# 2030_Switches.net
KiCad netlist of a schematic drawn in EAGLE
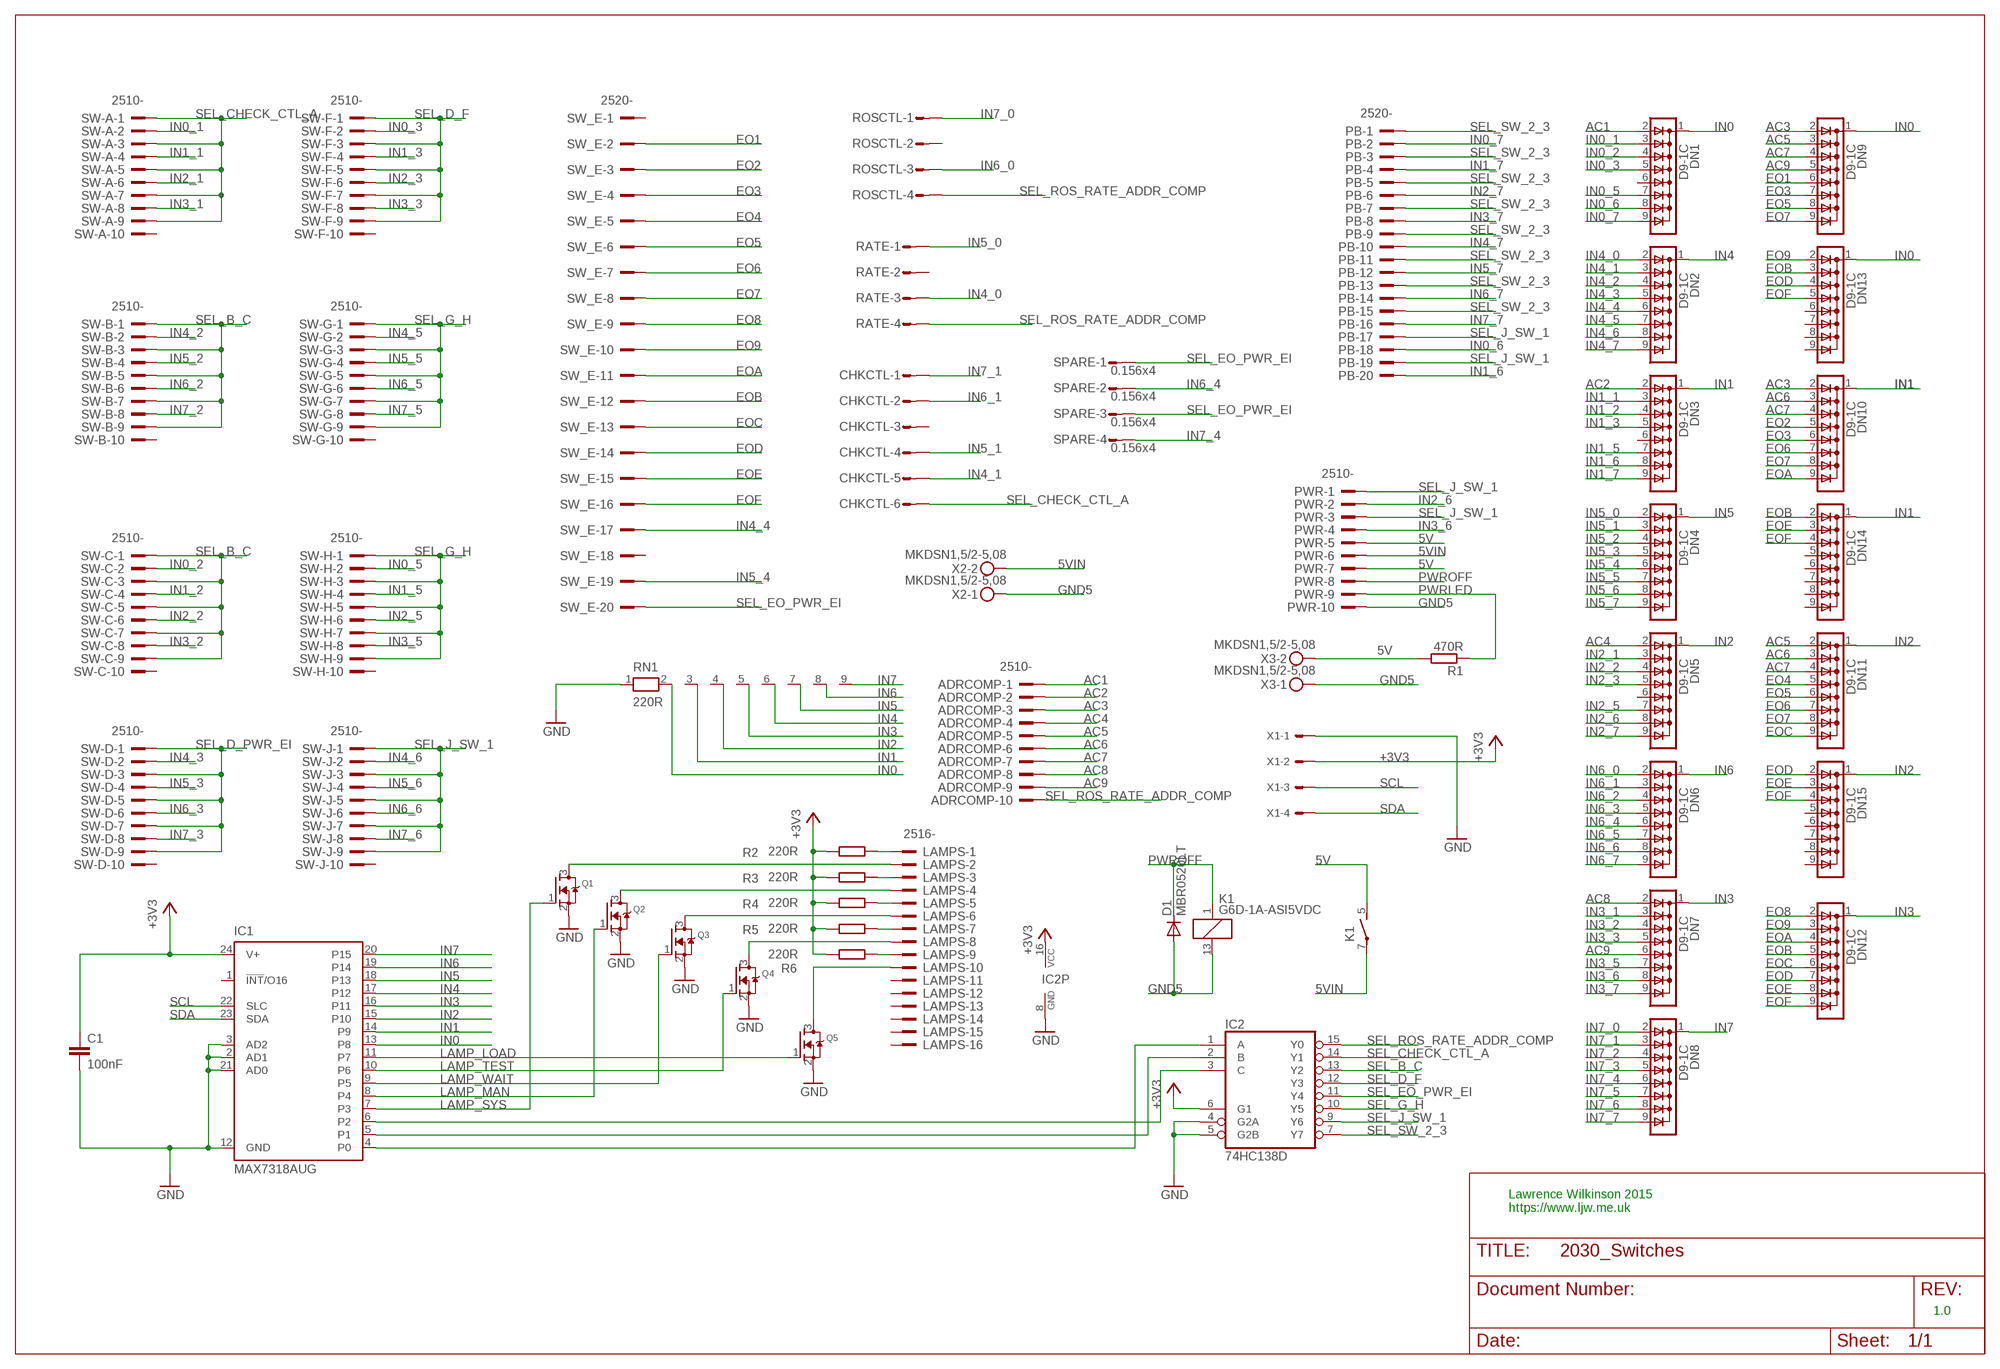
[diagram p0: schematic, sheet 1]

(export (version "E")
  (design (tool "Eeschema 10.0.6"))
  (components
    (comp (ref "ADRCOMP")
      (value "2510-")
      (footprint "eagle-import:PAK100_2500-10")
      (fields (field (name "MF") "3M") (field (name "MPN") "2510-6002UB"))
      (libsource (lib "eagle-import") (part "2510-"))
    )
    (comp (ref "C1")
      (value "100nF")
      (footprint "eagle-import:C1206")
      (libsource (lib "eagle-import") (part "C-EUC1206"))
    )
    (comp (ref "CHKCTL")
      (value "S06P")
      (footprint "eagle-import:S06P")
      (libsource (lib "eagle-import") (part "S06P"))
    )
    (comp (ref "D1")
      (value "MBR0520LT")
      (footprint "eagle-import:SOD123")
      (libsource (lib "eagle-import") (part "MBR0520LT"))
    )
    (comp (ref "DN1")
      (value "D9-1C")
      (footprint "eagle-import:SIL09C")
      (libsource (lib "eagle-import") (part "D9-1C"))
    )
    (comp (ref "DN2")
      (value "D9-1C")
      (footprint "eagle-import:SIL09C")
      (libsource (lib "eagle-import") (part "D9-1C"))
    )
    (comp (ref "DN3")
      (value "D9-1C")
      (footprint "eagle-import:SIL09C")
      (libsource (lib "eagle-import") (part "D9-1C"))
    )
    (comp (ref "DN4")
      (value "D9-1C")
      (footprint "eagle-import:SIL09C")
      (libsource (lib "eagle-import") (part "D9-1C"))
    )
    (comp (ref "DN5")
      (value "D9-1C")
      (footprint "eagle-import:SIL09C")
      (libsource (lib "eagle-import") (part "D9-1C"))
    )
    (comp (ref "DN6")
      (value "D9-1C")
      (footprint "eagle-import:SIL09C")
      (libsource (lib "eagle-import") (part "D9-1C"))
    )
    (comp (ref "DN7")
      (value "D9-1C")
      (footprint "eagle-import:SIL09C")
      (libsource (lib "eagle-import") (part "D9-1C"))
    )
    (comp (ref "DN8")
      (value "D9-1C")
      (footprint "eagle-import:SIL09C")
      (libsource (lib "eagle-import") (part "D9-1C"))
    )
    (comp (ref "DN9")
      (value "D9-1C")
      (footprint "eagle-import:SIL09C")
      (libsource (lib "eagle-import") (part "D9-1C"))
    )
    (comp (ref "DN10")
      (value "D9-1C")
      (footprint "eagle-import:SIL09C")
      (libsource (lib "eagle-import") (part "D9-1C"))
    )
    (comp (ref "DN11")
      (value "D9-1C")
      (footprint "eagle-import:SIL09C")
      (libsource (lib "eagle-import") (part "D9-1C"))
    )
    (comp (ref "DN12")
      (value "D9-1C")
      (footprint "eagle-import:SIL09C")
      (libsource (lib "eagle-import") (part "D9-1C"))
    )
    (comp (ref "DN13")
      (value "D9-1C")
      (footprint "eagle-import:SIL09C")
      (libsource (lib "eagle-import") (part "D9-1C"))
    )
    (comp (ref "DN14")
      (value "D9-1C")
      (footprint "eagle-import:SIL09C")
      (libsource (lib "eagle-import") (part "D9-1C"))
    )
    (comp (ref "DN15")
      (value "D9-1C")
      (footprint "eagle-import:SIL09C")
      (libsource (lib "eagle-import") (part "D9-1C"))
    )
    (comp (ref "IC1")
      (value "MAX7318AUG")
      (footprint "eagle-import:SO24L")
      (libsource (lib "eagle-import") (part "MAX7313AEGSOIC"))
    )
    (comp (ref "IC2")
      (value "74HC138D")
      (footprint "eagle-import:SO16")
      (libsource (lib "eagle-import") (part "74138DHC"))
    )
    (comp (ref "K1")
      (value "G6D-1A-ASI5VDC")
      (footprint "eagle-import:G6D")
      (libsource (lib "eagle-import") (part "G6D?-1A-ASI5VDC"))
    )
    (comp (ref "LAMPS")
      (value "2516-")
      (footprint "eagle-import:PAK100_2500-16")
      (libsource (lib "eagle-import") (part "2516-"))
    )
    (comp (ref "PB")
      (value "2520-")
      (footprint "eagle-import:PAK100_2500-20")
      (libsource (lib "eagle-import") (part "2520-"))
    )
    (comp (ref "PWR")
      (value "2510-")
      (footprint "eagle-import:PAK100_2500-10")
      (fields (field (name "MF") "3M") (field (name "MPN") "2510-6002UB"))
      (libsource (lib "eagle-import") (part "2510-"))
    )
    (comp (ref "Q1")
      (value "MOSFET-NREFLOW")
      (footprint "eagle-import:SOT23")
      (libsource (lib "eagle-import") (part "MOSFET-NREFLOW"))
    )
    (comp (ref "Q2")
      (value "MOSFET-NREFLOW")
      (footprint "eagle-import:SOT23")
      (libsource (lib "eagle-import") (part "MOSFET-NREFLOW"))
    )
    (comp (ref "Q3")
      (value "MOSFET-NREFLOW")
      (footprint "eagle-import:SOT23")
      (libsource (lib "eagle-import") (part "MOSFET-NREFLOW"))
    )
    (comp (ref "Q4")
      (value "MOSFET-NREFLOW")
      (footprint "eagle-import:SOT23")
      (libsource (lib "eagle-import") (part "MOSFET-NREFLOW"))
    )
    (comp (ref "Q5")
      (value "MOSFET-NREFLOW")
      (footprint "eagle-import:SOT23")
      (libsource (lib "eagle-import") (part "MOSFET-NREFLOW"))
    )
    (comp (ref "R1")
      (value "470R")
      (footprint "eagle-import:M1206")
      (libsource (lib "eagle-import") (part "R-EU_M1206"))
    )
    (comp (ref "R2")
      (value "220R")
      (footprint "eagle-import:R0805")
      (libsource (lib "eagle-import") (part "R-EU_R0805"))
    )
    (comp (ref "R3")
      (value "220R")
      (footprint "eagle-import:R0805")
      (libsource (lib "eagle-import") (part "R-EU_R0805"))
    )
    (comp (ref "R4")
      (value "220R")
      (footprint "eagle-import:R0805")
      (libsource (lib "eagle-import") (part "R-EU_R0805"))
    )
    (comp (ref "R5")
      (value "220R")
      (footprint "eagle-import:R0805")
      (libsource (lib "eagle-import") (part "R-EU_R0805"))
    )
    (comp (ref "R6")
      (value "220R")
      (footprint "eagle-import:R0805")
      (libsource (lib "eagle-import") (part "R-EU_R0805"))
    )
    (comp (ref "RATE")
      (value "S04P")
      (footprint "eagle-import:S04P")
      (libsource (lib "eagle-import") (part "S04P"))
    )
    (comp (ref "RN1")
      (value "220R")
      (footprint "eagle-import:RN-9")
      (libsource (lib "eagle-import") (part "RN08"))
    )
    (comp (ref "ROSCTL")
      (value "S04P")
      (footprint "eagle-import:S04P")
      (libsource (lib "eagle-import") (part "S04P"))
    )
    (comp (ref "SPARE")
      (value "0.156x4")
      (footprint "eagle-import:S04P")
      (libsource (lib "eagle-import") (part "S04P"))
    )
    (comp (ref "SW-A")
      (value "2510-")
      (footprint "eagle-import:PAK100_2500-10")
      (fields (field (name "MF") "3M") (field (name "MPN") "2510-6002UB"))
      (libsource (lib "eagle-import") (part "2510-"))
    )
    (comp (ref "SW-B")
      (value "2510-")
      (footprint "eagle-import:PAK100_2500-10")
      (fields (field (name "MF") "3M") (field (name "MPN") "2510-6002UB"))
      (libsource (lib "eagle-import") (part "2510-"))
    )
    (comp (ref "SW-C")
      (value "2510-")
      (footprint "eagle-import:PAK100_2500-10")
      (fields (field (name "MF") "3M") (field (name "MPN") "2510-6002UB"))
      (libsource (lib "eagle-import") (part "2510-"))
    )
    (comp (ref "SW-D")
      (value "2510-")
      (footprint "eagle-import:PAK100_2500-10")
      (fields (field (name "MF") "3M") (field (name "MPN") "2510-6002UB"))
      (libsource (lib "eagle-import") (part "2510-"))
    )
    (comp (ref "SW-F")
      (value "2510-")
      (footprint "eagle-import:PAK100_2500-10")
      (fields (field (name "MF") "3M") (field (name "MPN") "2510-6002UB"))
      (libsource (lib "eagle-import") (part "2510-"))
    )
    (comp (ref "SW-G")
      (value "2510-")
      (footprint "eagle-import:PAK100_2500-10")
      (fields (field (name "MF") "3M") (field (name "MPN") "2510-6002UB"))
      (libsource (lib "eagle-import") (part "2510-"))
    )
    (comp (ref "SW-H")
      (value "2510-")
      (footprint "eagle-import:PAK100_2500-10")
      (fields (field (name "MF") "3M") (field (name "MPN") "2510-6002UB"))
      (libsource (lib "eagle-import") (part "2510-"))
    )
    (comp (ref "SW-J")
      (value "2510-")
      (footprint "eagle-import:PAK100_2500-10")
      (fields (field (name "MF") "3M") (field (name "MPN") "2510-6002UB"))
      (libsource (lib "eagle-import") (part "2510-"))
    )
    (comp (ref "SW_E")
      (value "2520-")
      (footprint "eagle-import:PAK100_2500-20")
      (libsource (lib "eagle-import") (part "2520-"))
    )
    (comp (ref "X1")
      (value "KK-156-4")
      (footprint "eagle-import:KK-156-4")
      (libsource (lib "eagle-import") (part "KK-156-4"))
    )
    (comp (ref "X2")
      (value "MKDSN1,5/2-5,08")
      (footprint "eagle-import:MKDSN1,5_2-5,08")
      (libsource (lib "eagle-import") (part "MKDSN1,5/2-5,08"))
    )
    (comp (ref "X3")
      (value "MKDSN1,5/2-5,08")
      (footprint "eagle-import:MKDSN1,5_2-5,08")
      (libsource (lib "eagle-import") (part "MKDSN1,5/2-5,08"))
    )
  )
  (nets
    (net (code "1") (name "+3V3") (class "Default")
      (node (ref "C1") (pin "1") (pinfunction "1_1") (pintype "passive"))
      (node (ref "IC1") (pin "24") (pinfunction "V+_24") (pintype "power_in"))
      (node (ref "IC2") (pin "16") (pinfunction "VCC_16") (pintype "power_in"))
      (node (ref "IC2") (pin "6") (pinfunction "G1_6") (pintype "input"))
      (node (ref "R2") (pin "1") (pinfunction "1_1") (pintype "passive"))
      (node (ref "R3") (pin "1") (pinfunction "1_1") (pintype "passive"))
      (node (ref "R4") (pin "1") (pinfunction "1_1") (pintype "passive"))
      (node (ref "R5") (pin "1") (pinfunction "1_1") (pintype "passive"))
      (node (ref "R6") (pin "1") (pinfunction "1_1") (pintype "passive"))
      (node (ref "X1") (pin "2") (pinfunction "S_2") (pintype "passive"))
    )
    (net (code "2") (name "/5V") (class "Default")
      (node (ref "K1") (pin "5") (pinfunction "S_5") (pintype "passive"))
      (node (ref "PWR") (pin "5") (pinfunction "KL_5") (pintype "passive"))
      (node (ref "PWR") (pin "7") (pinfunction "KL_7") (pintype "passive"))
      (node (ref "R1") (pin "2") (pinfunction "2_2") (pintype "passive"))
      (node (ref "X3") (pin "2") (pinfunction "KL_2") (pintype "passive"))
    )
    (net (code "3") (name "/5VIN") (class "Default")
      (node (ref "K1") (pin "7") (pinfunction "P_7") (pintype "passive"))
      (node (ref "PWR") (pin "6") (pinfunction "KL_6") (pintype "passive"))
      (node (ref "X2") (pin "2") (pinfunction "KL_2") (pintype "passive"))
    )
    (net (code "4") (name "/AC1") (class "Default")
      (node (ref "ADRCOMP") (pin "1") (pinfunction "KL_1") (pintype "passive"))
      (node (ref "DN1") (pin "2") (pinfunction "2_2") (pintype "passive"))
    )
    (net (code "5") (name "/AC2") (class "Default")
      (node (ref "ADRCOMP") (pin "2") (pinfunction "KL_2") (pintype "passive"))
      (node (ref "DN3") (pin "2") (pinfunction "2_2") (pintype "passive"))
    )
    (net (code "6") (name "/AC3") (class "Default")
      (node (ref "ADRCOMP") (pin "3") (pinfunction "KL_3") (pintype "passive"))
      (node (ref "DN10") (pin "2") (pinfunction "2_2") (pintype "passive"))
      (node (ref "DN9") (pin "2") (pinfunction "2_2") (pintype "passive"))
    )
    (net (code "7") (name "/AC4") (class "Default")
      (node (ref "ADRCOMP") (pin "4") (pinfunction "KL_4") (pintype "passive"))
      (node (ref "DN5") (pin "2") (pinfunction "2_2") (pintype "passive"))
    )
    (net (code "8") (name "/AC5") (class "Default")
      (node (ref "ADRCOMP") (pin "5") (pinfunction "KL_5") (pintype "passive"))
      (node (ref "DN11") (pin "2") (pinfunction "2_2") (pintype "passive"))
      (node (ref "DN9") (pin "3") (pinfunction "3_3") (pintype "passive"))
    )
    (net (code "9") (name "/AC6") (class "Default")
      (node (ref "ADRCOMP") (pin "6") (pinfunction "KL_6") (pintype "passive"))
      (node (ref "DN10") (pin "3") (pinfunction "3_3") (pintype "passive"))
      (node (ref "DN11") (pin "3") (pinfunction "3_3") (pintype "passive"))
    )
    (net (code "10") (name "/AC7") (class "Default")
      (node (ref "ADRCOMP") (pin "7") (pinfunction "KL_7") (pintype "passive"))
      (node (ref "DN10") (pin "4") (pinfunction "4_4") (pintype "passive"))
      (node (ref "DN11") (pin "4") (pinfunction "4_4") (pintype "passive"))
      (node (ref "DN9") (pin "4") (pinfunction "4_4") (pintype "passive"))
    )
    (net (code "11") (name "/AC8") (class "Default")
      (node (ref "ADRCOMP") (pin "8") (pinfunction "KL_8") (pintype "passive"))
      (node (ref "DN7") (pin "2") (pinfunction "2_2") (pintype "passive"))
    )
    (net (code "12") (name "/AC9") (class "Default")
      (node (ref "ADRCOMP") (pin "9") (pinfunction "KL_9") (pintype "passive"))
      (node (ref "DN7") (pin "6") (pinfunction "6_6") (pintype "passive"))
      (node (ref "DN9") (pin "5") (pinfunction "5_5") (pintype "passive"))
    )
    (net (code "13") (name "/EO1") (class "Default")
      (node (ref "DN9") (pin "6") (pinfunction "6_6") (pintype "passive"))
      (node (ref "SW_E") (pin "2") (pinfunction "KL_2") (pintype "passive"))
    )
    (net (code "14") (name "/EO2") (class "Default")
      (node (ref "DN10") (pin "5") (pinfunction "5_5") (pintype "passive"))
      (node (ref "SW_E") (pin "3") (pinfunction "KL_3") (pintype "passive"))
    )
    (net (code "15") (name "/EO3") (class "Default")
      (node (ref "DN10") (pin "6") (pinfunction "6_6") (pintype "passive"))
      (node (ref "DN9") (pin "7") (pinfunction "7_7") (pintype "passive"))
      (node (ref "SW_E") (pin "4") (pinfunction "KL_4") (pintype "passive"))
    )
    (net (code "16") (name "/EO4") (class "Default")
      (node (ref "DN11") (pin "5") (pinfunction "5_5") (pintype "passive"))
      (node (ref "SW_E") (pin "5") (pinfunction "KL_5") (pintype "passive"))
    )
    (net (code "17") (name "/EO5") (class "Default")
      (node (ref "DN11") (pin "6") (pinfunction "6_6") (pintype "passive"))
      (node (ref "DN9") (pin "8") (pinfunction "8_8") (pintype "passive"))
      (node (ref "SW_E") (pin "6") (pinfunction "KL_6") (pintype "passive"))
    )
    (net (code "18") (name "/EO6") (class "Default")
      (node (ref "DN10") (pin "7") (pinfunction "7_7") (pintype "passive"))
      (node (ref "DN11") (pin "7") (pinfunction "7_7") (pintype "passive"))
      (node (ref "SW_E") (pin "7") (pinfunction "KL_7") (pintype "passive"))
    )
    (net (code "19") (name "/EO7") (class "Default")
      (node (ref "DN10") (pin "8") (pinfunction "8_8") (pintype "passive"))
      (node (ref "DN11") (pin "8") (pinfunction "8_8") (pintype "passive"))
      (node (ref "DN9") (pin "9") (pinfunction "9_9") (pintype "passive"))
      (node (ref "SW_E") (pin "8") (pinfunction "KL_8") (pintype "passive"))
    )
    (net (code "20") (name "/EO8") (class "Default")
      (node (ref "DN12") (pin "2") (pinfunction "2_2") (pintype "passive"))
      (node (ref "SW_E") (pin "9") (pinfunction "KL_9") (pintype "passive"))
    )
    (net (code "21") (name "/EO9") (class "Default")
      (node (ref "DN12") (pin "3") (pinfunction "3_3") (pintype "passive"))
      (node (ref "DN13") (pin "2") (pinfunction "2_2") (pintype "passive"))
      (node (ref "SW_E") (pin "10") (pinfunction "KL_10") (pintype "passive"))
    )
    (net (code "22") (name "/EOA") (class "Default")
      (node (ref "DN10") (pin "9") (pinfunction "9_9") (pintype "passive"))
      (node (ref "DN12") (pin "4") (pinfunction "4_4") (pintype "passive"))
      (node (ref "SW_E") (pin "11") (pinfunction "KL_11") (pintype "passive"))
    )
    (net (code "23") (name "/EOB") (class "Default")
      (node (ref "DN12") (pin "5") (pinfunction "5_5") (pintype "passive"))
      (node (ref "DN13") (pin "3") (pinfunction "3_3") (pintype "passive"))
      (node (ref "DN14") (pin "2") (pinfunction "2_2") (pintype "passive"))
      (node (ref "SW_E") (pin "12") (pinfunction "KL_12") (pintype "passive"))
    )
    (net (code "24") (name "/EOC") (class "Default")
      (node (ref "DN11") (pin "9") (pinfunction "9_9") (pintype "passive"))
      (node (ref "DN12") (pin "6") (pinfunction "6_6") (pintype "passive"))
      (node (ref "SW_E") (pin "13") (pinfunction "KL_13") (pintype "passive"))
    )
    (net (code "25") (name "/EOD") (class "Default")
      (node (ref "DN12") (pin "7") (pinfunction "7_7") (pintype "passive"))
      (node (ref "DN13") (pin "4") (pinfunction "4_4") (pintype "passive"))
      (node (ref "DN15") (pin "2") (pinfunction "2_2") (pintype "passive"))
      (node (ref "SW_E") (pin "14") (pinfunction "KL_14") (pintype "passive"))
    )
    (net (code "26") (name "/EOE") (class "Default")
      (node (ref "DN12") (pin "8") (pinfunction "8_8") (pintype "passive"))
      (node (ref "DN14") (pin "3") (pinfunction "3_3") (pintype "passive"))
      (node (ref "DN15") (pin "3") (pinfunction "3_3") (pintype "passive"))
      (node (ref "SW_E") (pin "15") (pinfunction "KL_15") (pintype "passive"))
    )
    (net (code "27") (name "/EOF") (class "Default")
      (node (ref "DN12") (pin "9") (pinfunction "9_9") (pintype "passive"))
      (node (ref "DN13") (pin "5") (pinfunction "5_5") (pintype "passive"))
      (node (ref "DN14") (pin "4") (pinfunction "4_4") (pintype "passive"))
      (node (ref "DN15") (pin "4") (pinfunction "4_4") (pintype "passive"))
      (node (ref "SW_E") (pin "16") (pinfunction "KL_16") (pintype "passive"))
    )
    (net (code "28") (name "/GND5") (class "Default")
      (node (ref "D1") (pin "A") (pinfunction "A_A") (pintype "passive"))
      (node (ref "K1") (pin "13") (pinfunction "2_13") (pintype "passive"))
      (node (ref "PWR") (pin "10") (pinfunction "KL_10") (pintype "passive"))
      (node (ref "X2") (pin "1") (pinfunction "KL_1") (pintype "passive"))
      (node (ref "X3") (pin "1") (pinfunction "KL_1") (pintype "passive"))
    )
    (net (code "29") (name "/IN0") (class "Default")
      (node (ref "DN1") (pin "1") (pinfunction "C_1") (pintype "passive"))
      (node (ref "DN13") (pin "1") (pinfunction "C_1") (pintype "passive"))
      (node (ref "DN9") (pin "1") (pinfunction "C_1") (pintype "passive"))
      (node (ref "IC1") (pin "13") (pinfunction "P8_13") (pintype "bidirectional"))
      (node (ref "RN1") (pin "2") (pinfunction "2_2") (pintype "passive"))
    )
    (net (code "30") (name "/IN0_1") (class "Default")
      (node (ref "DN1") (pin "3") (pinfunction "3_3") (pintype "passive"))
      (node (ref "SW-A") (pin "2") (pinfunction "KL_2") (pintype "passive"))
    )
    (net (code "31") (name "/IN0_2") (class "Default")
      (node (ref "DN1") (pin "4") (pinfunction "4_4") (pintype "passive"))
      (node (ref "SW-C") (pin "2") (pinfunction "KL_2") (pintype "passive"))
    )
    (net (code "32") (name "/IN0_3") (class "Default")
      (node (ref "DN1") (pin "5") (pinfunction "5_5") (pintype "passive"))
      (node (ref "SW-F") (pin "2") (pinfunction "KL_2") (pintype "passive"))
    )
    (net (code "33") (name "/IN0_5") (class "Default")
      (node (ref "DN1") (pin "7") (pinfunction "7_7") (pintype "passive"))
      (node (ref "SW-H") (pin "2") (pinfunction "KL_2") (pintype "passive"))
    )
    (net (code "34") (name "/IN0_6") (class "Default")
      (node (ref "DN1") (pin "8") (pinfunction "8_8") (pintype "passive"))
      (node (ref "PB") (pin "18") (pinfunction "KL_18") (pintype "passive"))
    )
    (net (code "35") (name "/IN0_7") (class "Default")
      (node (ref "DN1") (pin "9") (pinfunction "9_9") (pintype "passive"))
      (node (ref "PB") (pin "2") (pinfunction "KL_2") (pintype "passive"))
    )
    (net (code "36") (name "/IN1") (class "Default")
      (node (ref "DN10") (pin "1") (pinfunction "C_1") (pintype "passive"))
      (node (ref "DN14") (pin "1") (pinfunction "C_1") (pintype "passive"))
      (node (ref "DN3") (pin "1") (pinfunction "C_1") (pintype "passive"))
      (node (ref "IC1") (pin "14") (pinfunction "P9_14") (pintype "bidirectional"))
      (node (ref "RN1") (pin "3") (pinfunction "3_3") (pintype "passive"))
    )
    (net (code "37") (name "/IN1_1") (class "Default")
      (node (ref "DN3") (pin "3") (pinfunction "3_3") (pintype "passive"))
      (node (ref "SW-A") (pin "4") (pinfunction "KL_4") (pintype "passive"))
    )
    (net (code "38") (name "/IN1_2") (class "Default")
      (node (ref "DN3") (pin "4") (pinfunction "4_4") (pintype "passive"))
      (node (ref "SW-C") (pin "4") (pinfunction "KL_4") (pintype "passive"))
    )
    (net (code "39") (name "/IN1_3") (class "Default")
      (node (ref "DN3") (pin "5") (pinfunction "5_5") (pintype "passive"))
      (node (ref "SW-F") (pin "4") (pinfunction "KL_4") (pintype "passive"))
    )
    (net (code "40") (name "/IN1_5") (class "Default")
      (node (ref "DN3") (pin "7") (pinfunction "7_7") (pintype "passive"))
      (node (ref "SW-H") (pin "4") (pinfunction "KL_4") (pintype "passive"))
    )
    (net (code "41") (name "/IN1_6") (class "Default")
      (node (ref "DN3") (pin "8") (pinfunction "8_8") (pintype "passive"))
      (node (ref "PB") (pin "20") (pinfunction "KL_20") (pintype "passive"))
    )
    (net (code "42") (name "/IN1_7") (class "Default")
      (node (ref "DN3") (pin "9") (pinfunction "9_9") (pintype "passive"))
      (node (ref "PB") (pin "4") (pinfunction "KL_4") (pintype "passive"))
    )
    (net (code "43") (name "/IN2") (class "Default")
      (node (ref "DN11") (pin "1") (pinfunction "C_1") (pintype "passive"))
      (node (ref "DN15") (pin "1") (pinfunction "C_1") (pintype "passive"))
      (node (ref "DN5") (pin "1") (pinfunction "C_1") (pintype "passive"))
      (node (ref "IC1") (pin "15") (pinfunction "P10_15") (pintype "bidirectional"))
      (node (ref "RN1") (pin "4") (pinfunction "4_4") (pintype "passive"))
    )
    (net (code "44") (name "/IN2_1") (class "Default")
      (node (ref "DN5") (pin "3") (pinfunction "3_3") (pintype "passive"))
      (node (ref "SW-A") (pin "6") (pinfunction "KL_6") (pintype "passive"))
    )
    (net (code "45") (name "/IN2_2") (class "Default")
      (node (ref "DN5") (pin "4") (pinfunction "4_4") (pintype "passive"))
      (node (ref "SW-C") (pin "6") (pinfunction "KL_6") (pintype "passive"))
    )
    (net (code "46") (name "/IN2_3") (class "Default")
      (node (ref "DN5") (pin "5") (pinfunction "5_5") (pintype "passive"))
      (node (ref "SW-F") (pin "6") (pinfunction "KL_6") (pintype "passive"))
    )
    (net (code "47") (name "/IN2_5") (class "Default")
      (node (ref "DN5") (pin "7") (pinfunction "7_7") (pintype "passive"))
      (node (ref "SW-H") (pin "6") (pinfunction "KL_6") (pintype "passive"))
    )
    (net (code "48") (name "/IN2_6") (class "Default")
      (node (ref "DN5") (pin "8") (pinfunction "8_8") (pintype "passive"))
      (node (ref "PWR") (pin "2") (pinfunction "KL_2") (pintype "passive"))
    )
    (net (code "49") (name "/IN2_7") (class "Default")
      (node (ref "DN5") (pin "9") (pinfunction "9_9") (pintype "passive"))
      (node (ref "PB") (pin "6") (pinfunction "KL_6") (pintype "passive"))
    )
    (net (code "50") (name "/IN3") (class "Default")
      (node (ref "DN12") (pin "1") (pinfunction "C_1") (pintype "passive"))
      (node (ref "DN7") (pin "1") (pinfunction "C_1") (pintype "passive"))
      (node (ref "IC1") (pin "16") (pinfunction "P11_16") (pintype "bidirectional"))
      (node (ref "RN1") (pin "5") (pinfunction "5_5") (pintype "passive"))
    )
    (net (code "51") (name "/IN3_1") (class "Default")
      (node (ref "DN7") (pin "3") (pinfunction "3_3") (pintype "passive"))
      (node (ref "SW-A") (pin "8") (pinfunction "KL_8") (pintype "passive"))
    )
    (net (code "52") (name "/IN3_2") (class "Default")
      (node (ref "DN7") (pin "4") (pinfunction "4_4") (pintype "passive"))
      (node (ref "SW-C") (pin "8") (pinfunction "KL_8") (pintype "passive"))
    )
    (net (code "53") (name "/IN3_3") (class "Default")
      (node (ref "DN7") (pin "5") (pinfunction "5_5") (pintype "passive"))
      (node (ref "SW-F") (pin "8") (pinfunction "KL_8") (pintype "passive"))
    )
    (net (code "54") (name "/IN3_5") (class "Default")
      (node (ref "DN7") (pin "7") (pinfunction "7_7") (pintype "passive"))
      (node (ref "SW-H") (pin "8") (pinfunction "KL_8") (pintype "passive"))
    )
    (net (code "55") (name "/IN3_6") (class "Default")
      (node (ref "DN7") (pin "8") (pinfunction "8_8") (pintype "passive"))
      (node (ref "PWR") (pin "4") (pinfunction "KL_4") (pintype "passive"))
    )
    (net (code "56") (name "/IN3_7") (class "Default")
      (node (ref "DN7") (pin "9") (pinfunction "9_9") (pintype "passive"))
      (node (ref "PB") (pin "8") (pinfunction "KL_8") (pintype "passive"))
    )
    (net (code "57") (name "/IN4") (class "Default")
      (node (ref "DN2") (pin "1") (pinfunction "C_1") (pintype "passive"))
      (node (ref "IC1") (pin "17") (pinfunction "P12_17") (pintype "bidirectional"))
      (node (ref "RN1") (pin "6") (pinfunction "6_6") (pintype "passive"))
    )
    (net (code "58") (name "/IN4_0") (class "Default")
      (node (ref "DN2") (pin "2") (pinfunction "2_2") (pintype "passive"))
      (node (ref "RATE") (pin "3") (pinfunction "S_3") (pintype "passive"))
    )
    (net (code "59") (name "/IN4_1") (class "Default")
      (node (ref "CHKCTL") (pin "5") (pinfunction "S_5") (pintype "passive"))
      (node (ref "DN2") (pin "3") (pinfunction "3_3") (pintype "passive"))
    )
    (net (code "60") (name "/IN4_2") (class "Default")
      (node (ref "DN2") (pin "4") (pinfunction "4_4") (pintype "passive"))
      (node (ref "SW-B") (pin "2") (pinfunction "KL_2") (pintype "passive"))
    )
    (net (code "61") (name "/IN4_3") (class "Default")
      (node (ref "DN2") (pin "5") (pinfunction "5_5") (pintype "passive"))
      (node (ref "SW-D") (pin "2") (pinfunction "KL_2") (pintype "passive"))
    )
    (net (code "62") (name "/IN4_4") (class "Default")
      (node (ref "DN2") (pin "6") (pinfunction "6_6") (pintype "passive"))
      (node (ref "SW_E") (pin "17") (pinfunction "KL_17") (pintype "passive"))
    )
    (net (code "63") (name "/IN4_5") (class "Default")
      (node (ref "DN2") (pin "7") (pinfunction "7_7") (pintype "passive"))
      (node (ref "SW-G") (pin "2") (pinfunction "KL_2") (pintype "passive"))
    )
    (net (code "64") (name "/IN4_6") (class "Default")
      (node (ref "DN2") (pin "8") (pinfunction "8_8") (pintype "passive"))
      (node (ref "SW-J") (pin "2") (pinfunction "KL_2") (pintype "passive"))
    )
    (net (code "65") (name "/IN4_7") (class "Default")
      (node (ref "DN2") (pin "9") (pinfunction "9_9") (pintype "passive"))
      (node (ref "PB") (pin "10") (pinfunction "KL_10") (pintype "passive"))
    )
    (net (code "66") (name "/IN5") (class "Default")
      (node (ref "DN4") (pin "1") (pinfunction "C_1") (pintype "passive"))
      (node (ref "IC1") (pin "18") (pinfunction "P13_18") (pintype "bidirectional"))
      (node (ref "RN1") (pin "7") (pinfunction "7_7") (pintype "passive"))
    )
    (net (code "67") (name "/IN5_0") (class "Default")
      (node (ref "DN4") (pin "2") (pinfunction "2_2") (pintype "passive"))
      (node (ref "RATE") (pin "1") (pinfunction "S_1") (pintype "passive"))
    )
    (net (code "68") (name "/IN5_1") (class "Default")
      (node (ref "CHKCTL") (pin "4") (pinfunction "S_4") (pintype "passive"))
      (node (ref "DN4") (pin "3") (pinfunction "3_3") (pintype "passive"))
    )
    (net (code "69") (name "/IN5_2") (class "Default")
      (node (ref "DN4") (pin "4") (pinfunction "4_4") (pintype "passive"))
      (node (ref "SW-B") (pin "4") (pinfunction "KL_4") (pintype "passive"))
    )
    (net (code "70") (name "/IN5_3") (class "Default")
      (node (ref "DN4") (pin "5") (pinfunction "5_5") (pintype "passive"))
      (node (ref "SW-D") (pin "4") (pinfunction "KL_4") (pintype "passive"))
    )
    (net (code "71") (name "/IN5_4") (class "Default")
      (node (ref "DN4") (pin "6") (pinfunction "6_6") (pintype "passive"))
      (node (ref "SW_E") (pin "19") (pinfunction "KL_19") (pintype "passive"))
    )
    (net (code "72") (name "/IN5_5") (class "Default")
      (node (ref "DN4") (pin "7") (pinfunction "7_7") (pintype "passive"))
      (node (ref "SW-G") (pin "4") (pinfunction "KL_4") (pintype "passive"))
    )
    (net (code "73") (name "/IN5_6") (class "Default")
      (node (ref "DN4") (pin "8") (pinfunction "8_8") (pintype "passive"))
      (node (ref "SW-J") (pin "4") (pinfunction "KL_4") (pintype "passive"))
    )
    (net (code "74") (name "/IN5_7") (class "Default")
      (node (ref "DN4") (pin "9") (pinfunction "9_9") (pintype "passive"))
      (node (ref "PB") (pin "12") (pinfunction "KL_12") (pintype "passive"))
    )
    (net (code "75") (name "/IN6") (class "Default")
      (node (ref "DN6") (pin "1") (pinfunction "C_1") (pintype "passive"))
      (node (ref "IC1") (pin "19") (pinfunction "P14_19") (pintype "bidirectional"))
      (node (ref "RN1") (pin "8") (pinfunction "8_8") (pintype "passive"))
    )
    (net (code "76") (name "/IN6_0") (class "Default")
      (node (ref "DN6") (pin "2") (pinfunction "2_2") (pintype "passive"))
      (node (ref "ROSCTL") (pin "3") (pinfunction "S_3") (pintype "passive"))
    )
    (net (code "77") (name "/IN6_1") (class "Default")
      (node (ref "CHKCTL") (pin "2") (pinfunction "S_2") (pintype "passive"))
      (node (ref "DN6") (pin "3") (pinfunction "3_3") (pintype "passive"))
    )
    (net (code "78") (name "/IN6_2") (class "Default")
      (node (ref "DN6") (pin "4") (pinfunction "4_4") (pintype "passive"))
      (node (ref "SW-B") (pin "6") (pinfunction "KL_6") (pintype "passive"))
    )
    (net (code "79") (name "/IN6_3") (class "Default")
      (node (ref "DN6") (pin "5") (pinfunction "5_5") (pintype "passive"))
      (node (ref "SW-D") (pin "6") (pinfunction "KL_6") (pintype "passive"))
    )
    (net (code "80") (name "/IN6_4") (class "Default")
      (node (ref "DN6") (pin "6") (pinfunction "6_6") (pintype "passive"))
      (node (ref "SPARE") (pin "2") (pinfunction "S_2") (pintype "passive"))
    )
    (net (code "81") (name "/IN6_5") (class "Default")
      (node (ref "DN6") (pin "7") (pinfunction "7_7") (pintype "passive"))
      (node (ref "SW-G") (pin "6") (pinfunction "KL_6") (pintype "passive"))
    )
    (net (code "82") (name "/IN6_6") (class "Default")
      (node (ref "DN6") (pin "8") (pinfunction "8_8") (pintype "passive"))
      (node (ref "SW-J") (pin "6") (pinfunction "KL_6") (pintype "passive"))
    )
    (net (code "83") (name "/IN6_7") (class "Default")
      (node (ref "DN6") (pin "9") (pinfunction "9_9") (pintype "passive"))
      (node (ref "PB") (pin "14") (pinfunction "KL_14") (pintype "passive"))
    )
    (net (code "84") (name "/IN7") (class "Default")
      (node (ref "DN8") (pin "1") (pinfunction "C_1") (pintype "passive"))
      (node (ref "IC1") (pin "20") (pinfunction "P15_20") (pintype "bidirectional"))
      (node (ref "RN1") (pin "9") (pinfunction "9_9") (pintype "passive"))
    )
    (net (code "85") (name "/IN7_0") (class "Default")
      (node (ref "DN8") (pin "2") (pinfunction "2_2") (pintype "passive"))
      (node (ref "ROSCTL") (pin "1") (pinfunction "S_1") (pintype "passive"))
    )
    (net (code "86") (name "/IN7_1") (class "Default")
      (node (ref "CHKCTL") (pin "1") (pinfunction "S_1") (pintype "passive"))
      (node (ref "DN8") (pin "3") (pinfunction "3_3") (pintype "passive"))
    )
    (net (code "87") (name "/IN7_2") (class "Default")
      (node (ref "DN8") (pin "4") (pinfunction "4_4") (pintype "passive"))
      (node (ref "SW-B") (pin "8") (pinfunction "KL_8") (pintype "passive"))
    )
    (net (code "88") (name "/IN7_3") (class "Default")
      (node (ref "DN8") (pin "5") (pinfunction "5_5") (pintype "passive"))
      (node (ref "SW-D") (pin "8") (pinfunction "KL_8") (pintype "passive"))
    )
    (net (code "89") (name "/IN7_4") (class "Default")
      (node (ref "DN8") (pin "6") (pinfunction "6_6") (pintype "passive"))
      (node (ref "SPARE") (pin "4") (pinfunction "S_4") (pintype "passive"))
    )
    (net (code "90") (name "/IN7_5") (class "Default")
      (node (ref "DN8") (pin "7") (pinfunction "7_7") (pintype "passive"))
      (node (ref "SW-G") (pin "8") (pinfunction "KL_8") (pintype "passive"))
    )
    (net (code "91") (name "/IN7_6") (class "Default")
      (node (ref "DN8") (pin "8") (pinfunction "8_8") (pintype "passive"))
      (node (ref "SW-J") (pin "8") (pinfunction "KL_8") (pintype "passive"))
    )
    (net (code "92") (name "/IN7_7") (class "Default")
      (node (ref "DN8") (pin "9") (pinfunction "9_9") (pintype "passive"))
      (node (ref "PB") (pin "16") (pinfunction "KL_16") (pintype "passive"))
    )
    (net (code "93") (name "/LAMP_LOAD") (class "Default")
      (node (ref "IC1") (pin "11") (pinfunction "P7_11") (pintype "bidirectional"))
      (node (ref "Q5") (pin "1") (pinfunction "G_1") (pintype "bidirectional"))
    )
    (net (code "94") (name "/LAMP_MAN") (class "Default")
      (node (ref "IC1") (pin "8") (pinfunction "P4_8") (pintype "bidirectional"))
      (node (ref "Q2") (pin "1") (pinfunction "G_1") (pintype "bidirectional"))
    )
    (net (code "95") (name "/LAMP_SYS") (class "Default")
      (node (ref "IC1") (pin "7") (pinfunction "P3_7") (pintype "bidirectional"))
      (node (ref "Q1") (pin "1") (pinfunction "G_1") (pintype "bidirectional"))
    )
    (net (code "96") (name "/LAMP_TEST") (class "Default")
      (node (ref "IC1") (pin "10") (pinfunction "P6_10") (pintype "bidirectional"))
      (node (ref "Q4") (pin "1") (pinfunction "G_1") (pintype "bidirectional"))
    )
    (net (code "97") (name "/LAMP_WAIT") (class "Default")
      (node (ref "IC1") (pin "9") (pinfunction "P5_9") (pintype "bidirectional"))
      (node (ref "Q3") (pin "1") (pinfunction "G_1") (pintype "bidirectional"))
    )
    (net (code "98") (name "/PWRLED") (class "Default")
      (node (ref "PWR") (pin "9") (pinfunction "KL_9") (pintype "passive"))
      (node (ref "R1") (pin "1") (pinfunction "1_1") (pintype "passive"))
    )
    (net (code "99") (name "/PWROFF") (class "Default")
      (node (ref "D1") (pin "C") (pinfunction "C_C") (pintype "passive"))
      (node (ref "K1") (pin "1") (pinfunction "1_1") (pintype "passive"))
      (node (ref "PWR") (pin "8") (pinfunction "KL_8") (pintype "passive"))
    )
    (net (code "100") (name "/SCL") (class "Default")
      (node (ref "IC1") (pin "22") (pinfunction "SLC_22") (pintype "input"))
      (node (ref "X1") (pin "3") (pinfunction "S_3") (pintype "passive"))
    )
    (net (code "101") (name "/SDA") (class "Default")
      (node (ref "IC1") (pin "23") (pinfunction "SDA_23") (pintype "bidirectional"))
      (node (ref "X1") (pin "4") (pinfunction "S_4") (pintype "passive"))
    )
    (net (code "102") (name "/SEL_B_C") (class "Default")
      (node (ref "IC2") (pin "13") (pinfunction "Y2_13") (pintype "output"))
      (node (ref "SW-B") (pin "1") (pinfunction "KL_1") (pintype "passive"))
      (node (ref "SW-B") (pin "3") (pinfunction "KL_3") (pintype "passive"))
      (node (ref "SW-B") (pin "5") (pinfunction "KL_5") (pintype "passive"))
      (node (ref "SW-B") (pin "7") (pinfunction "KL_7") (pintype "passive"))
      (node (ref "SW-B") (pin "9") (pinfunction "KL_9") (pintype "passive"))
      (node (ref "SW-C") (pin "1") (pinfunction "KL_1") (pintype "passive"))
      (node (ref "SW-C") (pin "3") (pinfunction "KL_3") (pintype "passive"))
      (node (ref "SW-C") (pin "5") (pinfunction "KL_5") (pintype "passive"))
      (node (ref "SW-C") (pin "7") (pinfunction "KL_7") (pintype "passive"))
      (node (ref "SW-C") (pin "9") (pinfunction "KL_9") (pintype "passive"))
    )
    (net (code "103") (name "/SEL_CHECK_CTL_A") (class "Default")
      (node (ref "CHKCTL") (pin "6") (pinfunction "S_6") (pintype "passive"))
      (node (ref "IC2") (pin "14") (pinfunction "Y1_14") (pintype "output"))
      (node (ref "SW-A") (pin "1") (pinfunction "KL_1") (pintype "passive"))
      (node (ref "SW-A") (pin "3") (pinfunction "KL_3") (pintype "passive"))
      (node (ref "SW-A") (pin "5") (pinfunction "KL_5") (pintype "passive"))
      (node (ref "SW-A") (pin "7") (pinfunction "KL_7") (pintype "passive"))
      (node (ref "SW-A") (pin "9") (pinfunction "KL_9") (pintype "passive"))
    )
    (net (code "104") (name "/SEL_D_F") (class "Default")
      (node (ref "IC2") (pin "12") (pinfunction "Y3_12") (pintype "output"))
      (node (ref "SW-F") (pin "1") (pinfunction "KL_1") (pintype "passive"))
      (node (ref "SW-F") (pin "3") (pinfunction "KL_3") (pintype "passive"))
      (node (ref "SW-F") (pin "5") (pinfunction "KL_5") (pintype "passive"))
      (node (ref "SW-F") (pin "7") (pinfunction "KL_7") (pintype "passive"))
      (node (ref "SW-F") (pin "9") (pinfunction "KL_9") (pintype "passive"))
    )
    (net (code "105") (name "/SEL_D_PWR_EI") (class "Default")
      (node (ref "SW-D") (pin "1") (pinfunction "KL_1") (pintype "passive"))
      (node (ref "SW-D") (pin "3") (pinfunction "KL_3") (pintype "passive"))
      (node (ref "SW-D") (pin "5") (pinfunction "KL_5") (pintype "passive"))
      (node (ref "SW-D") (pin "7") (pinfunction "KL_7") (pintype "passive"))
      (node (ref "SW-D") (pin "9") (pinfunction "KL_9") (pintype "passive"))
    )
    (net (code "106") (name "/SEL_EO_PWR_EI") (class "Default")
      (node (ref "IC2") (pin "11") (pinfunction "Y4_11") (pintype "output"))
      (node (ref "SPARE") (pin "1") (pinfunction "S_1") (pintype "passive"))
      (node (ref "SPARE") (pin "3") (pinfunction "S_3") (pintype "passive"))
      (node (ref "SW_E") (pin "20") (pinfunction "KL_20") (pintype "passive"))
    )
    (net (code "107") (name "/SEL_G_H") (class "Default")
      (node (ref "IC2") (pin "10") (pinfunction "Y5_10") (pintype "output"))
      (node (ref "SW-G") (pin "1") (pinfunction "KL_1") (pintype "passive"))
      (node (ref "SW-G") (pin "3") (pinfunction "KL_3") (pintype "passive"))
      (node (ref "SW-G") (pin "5") (pinfunction "KL_5") (pintype "passive"))
      (node (ref "SW-G") (pin "7") (pinfunction "KL_7") (pintype "passive"))
      (node (ref "SW-G") (pin "9") (pinfunction "KL_9") (pintype "passive"))
      (node (ref "SW-H") (pin "1") (pinfunction "KL_1") (pintype "passive"))
      (node (ref "SW-H") (pin "3") (pinfunction "KL_3") (pintype "passive"))
      (node (ref "SW-H") (pin "5") (pinfunction "KL_5") (pintype "passive"))
      (node (ref "SW-H") (pin "7") (pinfunction "KL_7") (pintype "passive"))
      (node (ref "SW-H") (pin "9") (pinfunction "KL_9") (pintype "passive"))
    )
    (net (code "108") (name "/SEL_J_SW_1") (class "Default")
      (node (ref "IC2") (pin "9") (pinfunction "Y6_9") (pintype "output"))
      (node (ref "PB") (pin "17") (pinfunction "KL_17") (pintype "passive"))
      (node (ref "PB") (pin "19") (pinfunction "KL_19") (pintype "passive"))
      (node (ref "PWR") (pin "1") (pinfunction "KL_1") (pintype "passive"))
      (node (ref "PWR") (pin "3") (pinfunction "KL_3") (pintype "passive"))
      (node (ref "SW-J") (pin "1") (pinfunction "KL_1") (pintype "passive"))
      (node (ref "SW-J") (pin "3") (pinfunction "KL_3") (pintype "passive"))
      (node (ref "SW-J") (pin "5") (pinfunction "KL_5") (pintype "passive"))
      (node (ref "SW-J") (pin "7") (pinfunction "KL_7") (pintype "passive"))
      (node (ref "SW-J") (pin "9") (pinfunction "KL_9") (pintype "passive"))
    )
    (net (code "109") (name "/SEL_ROS_RATE_ADDR_COMP") (class "Default")
      (node (ref "ADRCOMP") (pin "10") (pinfunction "KL_10") (pintype "passive"))
      (node (ref "IC2") (pin "15") (pinfunction "Y0_15") (pintype "output"))
      (node (ref "RATE") (pin "4") (pinfunction "S_4") (pintype "passive"))
      (node (ref "ROSCTL") (pin "4") (pinfunction "S_4") (pintype "passive"))
    )
    (net (code "110") (name "/SEL_SW_2_3") (class "Default")
      (node (ref "IC2") (pin "7") (pinfunction "Y7_7") (pintype "output"))
      (node (ref "PB") (pin "1") (pinfunction "KL_1") (pintype "passive"))
      (node (ref "PB") (pin "11") (pinfunction "KL_11") (pintype "passive"))
      (node (ref "PB") (pin "13") (pinfunction "KL_13") (pintype "passive"))
      (node (ref "PB") (pin "15") (pinfunction "KL_15") (pintype "passive"))
      (node (ref "PB") (pin "3") (pinfunction "KL_3") (pintype "passive"))
      (node (ref "PB") (pin "5") (pinfunction "KL_5") (pintype "passive"))
      (node (ref "PB") (pin "7") (pinfunction "KL_7") (pintype "passive"))
      (node (ref "PB") (pin "9") (pinfunction "KL_9") (pintype "passive"))
    )
    (net (code "111") (name "GND") (class "Default")
      (node (ref "C1") (pin "2") (pinfunction "2_2") (pintype "passive"))
      (node (ref "IC1") (pin "12") (pinfunction "GND_12") (pintype "power_in"))
      (node (ref "IC1") (pin "2") (pinfunction "AD1_2") (pintype "input"))
      (node (ref "IC1") (pin "21") (pinfunction "AD0_21") (pintype "input"))
      (node (ref "IC1") (pin "3") (pinfunction "AD2_3") (pintype "input"))
      (node (ref "IC2") (pin "4") (pinfunction "G2A_4") (pintype "input"))
      (node (ref "IC2") (pin "5") (pinfunction "G2B_5") (pintype "input"))
      (node (ref "IC2") (pin "8") (pinfunction "GND_8") (pintype "power_in"))
      (node (ref "Q1") (pin "2") (pinfunction "S_2") (pintype "bidirectional"))
      (node (ref "Q2") (pin "2") (pinfunction "S_2") (pintype "bidirectional"))
      (node (ref "Q3") (pin "2") (pinfunction "S_2") (pintype "bidirectional"))
      (node (ref "Q4") (pin "2") (pinfunction "S_2") (pintype "bidirectional"))
      (node (ref "Q5") (pin "2") (pinfunction "S_2") (pintype "bidirectional"))
      (node (ref "RN1") (pin "1") (pinfunction "1_1") (pintype "passive"))
      (node (ref "X1") (pin "1") (pinfunction "S_1") (pintype "passive"))
    )
    (net (code "112") (name "Net-(IC1-P0)") (class "Default")
      (node (ref "IC1") (pin "4") (pinfunction "P0_4") (pintype "bidirectional"))
      (node (ref "IC2") (pin "1") (pinfunction "A_1") (pintype "input"))
    )
    (net (code "113") (name "Net-(IC1-P1)") (class "Default")
      (node (ref "IC1") (pin "5") (pinfunction "P1_5") (pintype "bidirectional"))
      (node (ref "IC2") (pin "2") (pinfunction "B_2") (pintype "input"))
    )
    (net (code "114") (name "Net-(IC1-P2)") (class "Default")
      (node (ref "IC1") (pin "6") (pinfunction "P2_6") (pintype "bidirectional"))
      (node (ref "IC2") (pin "3") (pinfunction "C_3") (pintype "input"))
    )
    (net (code "115") (name "Net-(LAMPSA-KL)") (class "Default")
      (node (ref "LAMPS") (pin "1") (pinfunction "KL_1") (pintype "passive"))
      (node (ref "R2") (pin "2") (pinfunction "2_2") (pintype "passive"))
    )
    (net (code "116") (name "Net-(LAMPSB-KL)") (class "Default")
      (node (ref "LAMPS") (pin "10") (pinfunction "KL_10") (pintype "passive"))
      (node (ref "Q5") (pin "3") (pinfunction "D_3") (pintype "bidirectional"))
    )
    (net (code "117") (name "Net-(LAMPSI-KL)") (class "Default")
      (node (ref "LAMPS") (pin "2") (pinfunction "KL_2") (pintype "passive"))
      (node (ref "Q1") (pin "3") (pinfunction "D_3") (pintype "bidirectional"))
    )
    (net (code "118") (name "Net-(LAMPSJ-KL)") (class "Default")
      (node (ref "LAMPS") (pin "3") (pinfunction "KL_3") (pintype "passive"))
      (node (ref "R3") (pin "2") (pinfunction "2_2") (pintype "passive"))
    )
    (net (code "119") (name "Net-(LAMPSK-KL)") (class "Default")
      (node (ref "LAMPS") (pin "4") (pinfunction "KL_4") (pintype "passive"))
      (node (ref "Q2") (pin "3") (pinfunction "D_3") (pintype "bidirectional"))
    )
    (net (code "120") (name "Net-(LAMPSL-KL)") (class "Default")
      (node (ref "LAMPS") (pin "5") (pinfunction "KL_5") (pintype "passive"))
      (node (ref "R4") (pin "2") (pinfunction "2_2") (pintype "passive"))
    )
    (net (code "121") (name "Net-(LAMPSM-KL)") (class "Default")
      (node (ref "LAMPS") (pin "6") (pinfunction "KL_6") (pintype "passive"))
      (node (ref "Q3") (pin "3") (pinfunction "D_3") (pintype "bidirectional"))
    )
    (net (code "122") (name "Net-(LAMPSN-KL)") (class "Default")
      (node (ref "LAMPS") (pin "7") (pinfunction "KL_7") (pintype "passive"))
      (node (ref "R5") (pin "2") (pinfunction "2_2") (pintype "passive"))
    )
    (net (code "123") (name "Net-(LAMPSO-KL)") (class "Default")
      (node (ref "LAMPS") (pin "8") (pinfunction "KL_8") (pintype "passive"))
      (node (ref "Q4") (pin "3") (pinfunction "D_3") (pintype "bidirectional"))
    )
    (net (code "124") (name "Net-(LAMPSP-KL)") (class "Default")
      (node (ref "LAMPS") (pin "9") (pinfunction "KL_9") (pintype "passive"))
      (node (ref "R6") (pin "2") (pinfunction "2_2") (pintype "passive"))
    )
    (net (code "125") (name "unconnected-(CHKCTLC-S-Pad3)") (class "Default")
      (node (ref "CHKCTL") (pin "3") (pinfunction "S_3") (pintype "passive"))
    )
    (net (code "126") (name "unconnected-(DN1-Pad6)") (class "Default")
      (node (ref "DN1") (pin "6") (pinfunction "6_6") (pintype "passive"))
    )
    (net (code "127") (name "unconnected-(DN3-Pad6)") (class "Default")
      (node (ref "DN3") (pin "6") (pinfunction "6_6") (pintype "passive"))
    )
    (net (code "128") (name "unconnected-(DN5-Pad6)") (class "Default")
      (node (ref "DN5") (pin "6") (pinfunction "6_6") (pintype "passive"))
    )
    (net (code "129") (name "unconnected-(DN13-Pad6)") (class "Default")
      (node (ref "DN13") (pin "6") (pinfunction "6_6") (pintype "passive"))
    )
    (net (code "130") (name "unconnected-(DN13-Pad7)") (class "Default")
      (node (ref "DN13") (pin "7") (pinfunction "7_7") (pintype "passive"))
    )
    (net (code "131") (name "unconnected-(DN13-Pad8)") (class "Default")
      (node (ref "DN13") (pin "8") (pinfunction "8_8") (pintype "passive"))
    )
    (net (code "132") (name "unconnected-(DN13-Pad9)") (class "Default")
      (node (ref "DN13") (pin "9") (pinfunction "9_9") (pintype "passive"))
    )
    (net (code "133") (name "unconnected-(DN14-Pad5)") (class "Default")
      (node (ref "DN14") (pin "5") (pinfunction "5_5") (pintype "passive"))
    )
    (net (code "134") (name "unconnected-(DN14-Pad6)") (class "Default")
      (node (ref "DN14") (pin "6") (pinfunction "6_6") (pintype "passive"))
    )
    (net (code "135") (name "unconnected-(DN14-Pad7)") (class "Default")
      (node (ref "DN14") (pin "7") (pinfunction "7_7") (pintype "passive"))
    )
    (net (code "136") (name "unconnected-(DN14-Pad8)") (class "Default")
      (node (ref "DN14") (pin "8") (pinfunction "8_8") (pintype "passive"))
    )
    (net (code "137") (name "unconnected-(DN14-Pad9)") (class "Default")
      (node (ref "DN14") (pin "9") (pinfunction "9_9") (pintype "passive"))
    )
    (net (code "138") (name "unconnected-(DN15-Pad5)") (class "Default")
      (node (ref "DN15") (pin "5") (pinfunction "5_5") (pintype "passive"))
    )
    (net (code "139") (name "unconnected-(DN15-Pad6)") (class "Default")
      (node (ref "DN15") (pin "6") (pinfunction "6_6") (pintype "passive"))
    )
    (net (code "140") (name "unconnected-(DN15-Pad7)") (class "Default")
      (node (ref "DN15") (pin "7") (pinfunction "7_7") (pintype "passive"))
    )
    (net (code "141") (name "unconnected-(DN15-Pad8)") (class "Default")
      (node (ref "DN15") (pin "8") (pinfunction "8_8") (pintype "passive"))
    )
    (net (code "142") (name "unconnected-(DN15-Pad9)") (class "Default")
      (node (ref "DN15") (pin "9") (pinfunction "9_9") (pintype "passive"))
    )
    (net (code "143") (name "unconnected-(IC1-~{INT}{slash}O16-Pad1)") (class "Default")
      (node (ref "IC1") (pin "1") (pinfunction "~{INT}/O16_1") (pintype "open_collector"))
    )
    (net (code "144") (name "unconnected-(LAMPSC-KL-Pad11)") (class "Default")
      (node (ref "LAMPS") (pin "11") (pinfunction "KL_11") (pintype "passive"))
    )
    (net (code "145") (name "unconnected-(LAMPSD-KL-Pad12)") (class "Default")
      (node (ref "LAMPS") (pin "12") (pinfunction "KL_12") (pintype "passive"))
    )
    (net (code "146") (name "unconnected-(LAMPSE-KL-Pad13)") (class "Default")
      (node (ref "LAMPS") (pin "13") (pinfunction "KL_13") (pintype "passive"))
    )
    (net (code "147") (name "unconnected-(LAMPSF-KL-Pad14)") (class "Default")
      (node (ref "LAMPS") (pin "14") (pinfunction "KL_14") (pintype "passive"))
    )
    (net (code "148") (name "unconnected-(LAMPSG-KL-Pad15)") (class "Default")
      (node (ref "LAMPS") (pin "15") (pinfunction "KL_15") (pintype "passive"))
    )
    (net (code "149") (name "unconnected-(LAMPSH-KL-Pad16)") (class "Default")
      (node (ref "LAMPS") (pin "16") (pinfunction "KL_16") (pintype "passive"))
    )
    (net (code "150") (name "unconnected-(RATEB-S-Pad2)") (class "Default")
      (node (ref "RATE") (pin "2") (pinfunction "S_2") (pintype "passive"))
    )
    (net (code "151") (name "unconnected-(ROSCTLB-S-Pad2)") (class "Default")
      (node (ref "ROSCTL") (pin "2") (pinfunction "S_2") (pintype "passive"))
    )
    (net (code "152") (name "unconnected-(SW-AB-KL-Pad10)") (class "Default")
      (node (ref "SW-A") (pin "10") (pinfunction "KL_10") (pintype "passive"))
    )
    (net (code "153") (name "unconnected-(SW-BB-KL-Pad10)") (class "Default")
      (node (ref "SW-B") (pin "10") (pinfunction "KL_10") (pintype "passive"))
    )
    (net (code "154") (name "unconnected-(SW-CB-KL-Pad10)") (class "Default")
      (node (ref "SW-C") (pin "10") (pinfunction "KL_10") (pintype "passive"))
    )
    (net (code "155") (name "unconnected-(SW-DB-KL-Pad10)") (class "Default")
      (node (ref "SW-D") (pin "10") (pinfunction "KL_10") (pintype "passive"))
    )
    (net (code "156") (name "unconnected-(SW-FB-KL-Pad10)") (class "Default")
      (node (ref "SW-F") (pin "10") (pinfunction "KL_10") (pintype "passive"))
    )
    (net (code "157") (name "unconnected-(SW-GB-KL-Pad10)") (class "Default")
      (node (ref "SW-G") (pin "10") (pinfunction "KL_10") (pintype "passive"))
    )
    (net (code "158") (name "unconnected-(SW-HB-KL-Pad10)") (class "Default")
      (node (ref "SW-H") (pin "10") (pinfunction "KL_10") (pintype "passive"))
    )
    (net (code "159") (name "unconnected-(SW-JB-KL-Pad10)") (class "Default")
      (node (ref "SW-J") (pin "10") (pinfunction "KL_10") (pintype "passive"))
    )
    (net (code "160") (name "unconnected-(SW_EA-KL-Pad1)") (class "Default")
      (node (ref "SW_E") (pin "1") (pinfunction "KL_1") (pintype "passive"))
    )
    (net (code "161") (name "unconnected-(SW_EJ-KL-Pad18)") (class "Default")
      (node (ref "SW_E") (pin "18") (pinfunction "KL_18") (pintype "passive"))
    )
  )
)
